# stepper_motor_driver_schem.net
KiCad netlist of a schematic drawn in EAGLE
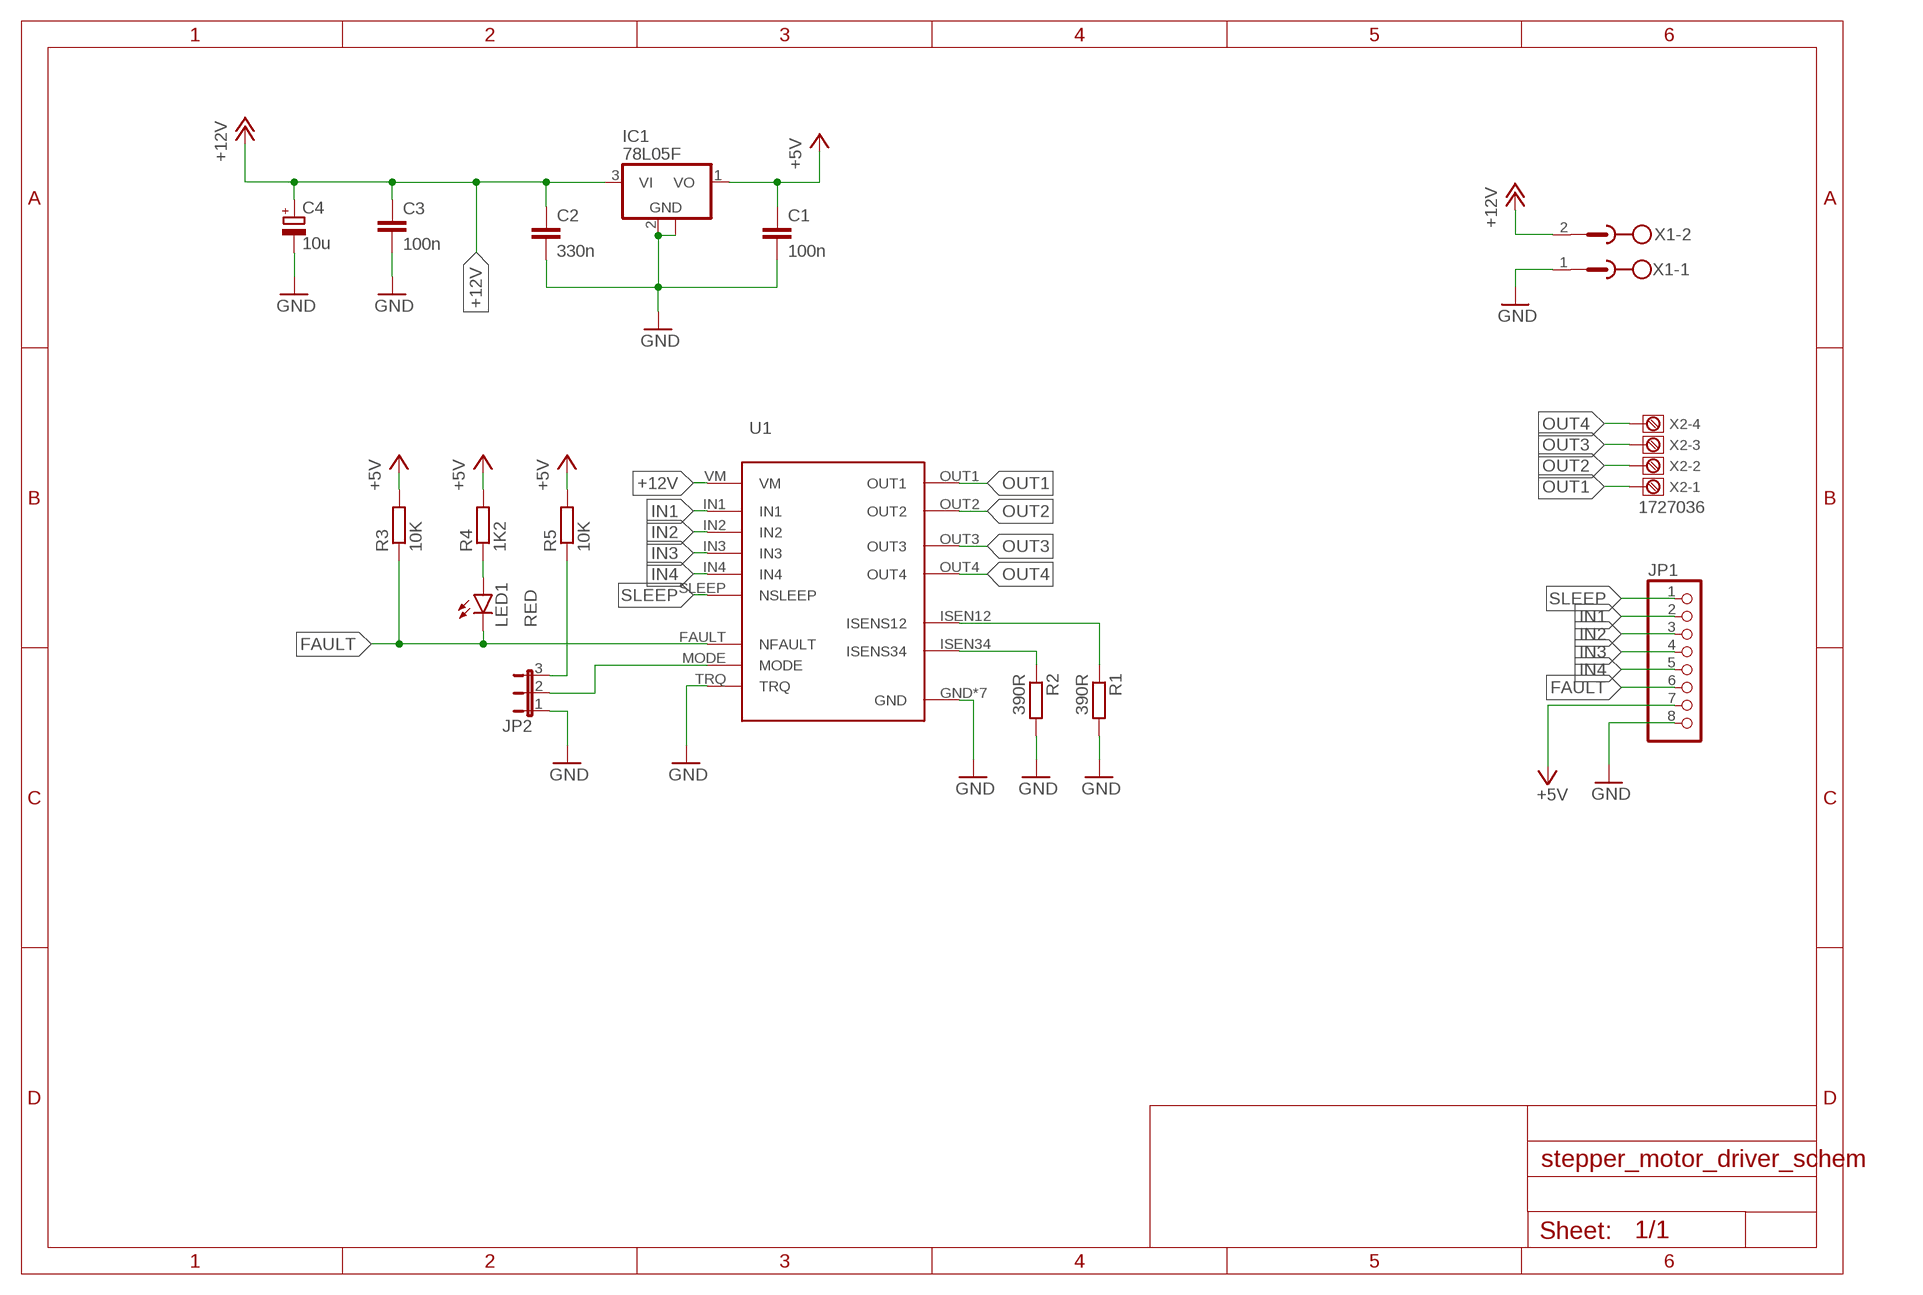
[diagram p0: schematic, sheet 1]

(export (version "E")
  (design (tool "Eeschema 10.0.6"))
  (components
    (comp (ref "C1")
      (value "100n")
      (footprint "eagle-import:C0402")
      (libsource (lib "eagle-import") (part "C-EUC0402"))
    )
    (comp (ref "C2")
      (value "330n")
      (footprint "eagle-import:C0402")
      (libsource (lib "eagle-import") (part "C-EUC0402"))
    )
    (comp (ref "C3")
      (value "100n")
      (footprint "eagle-import:C0402")
      (libsource (lib "eagle-import") (part "C-EUC0402"))
    )
    (comp (ref "C4")
      (value "10u")
      (footprint "eagle-import:E2-5")
      (libsource (lib "eagle-import") (part "CPOL-EUE2-5"))
    )
    (comp (ref "IC1")
      (value "78L05F")
      (footprint "eagle-import:SOT89")
      (libsource (lib "eagle-import") (part "78LF05"))
    )
    (comp (ref "JP1")
      (value "PINHD-1X8")
      (footprint "eagle-import:1X08")
      (libsource (lib "eagle-import") (part "PINHD-1X8"))
    )
    (comp (ref "JP2")
      (value "JP2E")
      (footprint "eagle-import:JP2")
      (libsource (lib "eagle-import") (part "JP2E"))
    )
    (comp (ref "LED1")
      (value "RED")
      (footprint "eagle-import:CHIP-LED0603")
      (libsource (lib "eagle-import") (part "LEDCHIP-LED0603"))
    )
    (comp (ref "R1")
      (value "390R")
      (footprint "eagle-import:R1206")
      (libsource (lib "eagle-import") (part "R-EU_R1206"))
    )
    (comp (ref "R2")
      (value "390R")
      (footprint "eagle-import:R1206")
      (libsource (lib "eagle-import") (part "R-EU_R1206"))
    )
    (comp (ref "R3")
      (value "10K")
      (footprint "eagle-import:R0603")
      (libsource (lib "eagle-import") (part "R-EU_R0603"))
    )
    (comp (ref "R4")
      (value "1K2")
      (footprint "eagle-import:R0603")
      (libsource (lib "eagle-import") (part "R-EU_R0603"))
    )
    (comp (ref "R5")
      (value "10K")
      (footprint "eagle-import:R0603")
      (libsource (lib "eagle-import") (part "R-EU_R0603"))
    )
    (comp (ref "U1")
      (value "DRV8847RTER")
      (footprint "eagle-import:DRV8847RTER")
      (libsource (lib "eagle-import") (part "DRV8847RTER"))
    )
    (comp (ref "X1")
      (value "MSTBV2")
      (footprint "eagle-import:MSTBV2")
      (libsource (lib "eagle-import") (part "MSTBV2"))
    )
    (comp (ref "X2")
      (value "1727036")
      (footprint "eagle-import:1727036")
      (fields (field (name "MF") "FARNELL"))
      (libsource (lib "eagle-import") (part "1727036"))
    )
  )
  (nets
    (net (code "1") (name "+5V") (class "Default")
      (node (ref "C1") (pin "1") (pinfunction "1_1") (pintype "passive"))
      (node (ref "IC1") (pin "1") (pinfunction "VO_1") (pintype "passive"))
      (node (ref "JP1") (pin "7") (pinfunction "7_7") (pintype "passive"))
      (node (ref "R3") (pin "2") (pinfunction "2_2") (pintype "passive"))
      (node (ref "R4") (pin "2") (pinfunction "2_2") (pintype "passive"))
      (node (ref "R5") (pin "2") (pinfunction "2_2") (pintype "passive"))
    )
    (net (code "2") (name "+12V") (class "Default")
      (node (ref "C2") (pin "1") (pinfunction "1_1") (pintype "passive"))
      (node (ref "C3") (pin "1") (pinfunction "1_1") (pintype "passive"))
      (node (ref "C4") (pin "+") (pinfunction "+_+") (pintype "passive"))
      (node (ref "IC1") (pin "3") (pinfunction "VI_3") (pintype "input"))
      (node (ref "U1") (pin "VM") (pinfunction "VM_VM") (pintype "bidirectional"))
      (node (ref "X1") (pin "2") (pinfunction "SK_2") (pintype "passive"))
    )
    (net (code "3") (name "FAULT") (class "Default")
      (node (ref "JP1") (pin "6") (pinfunction "6_6") (pintype "passive"))
      (node (ref "LED1") (pin "C") (pinfunction "C_C") (pintype "passive"))
      (node (ref "R3") (pin "1") (pinfunction "1_1") (pintype "passive"))
      (node (ref "U1") (pin "FAULT") (pinfunction "NFAULT_FAULT") (pintype "bidirectional"))
    )
    (net (code "4") (name "GND") (class "Default")
      (node (ref "C1") (pin "2") (pinfunction "2_2") (pintype "passive"))
      (node (ref "C2") (pin "2") (pinfunction "2_2") (pintype "passive"))
      (node (ref "C3") (pin "2") (pinfunction "2_2") (pintype "passive"))
      (node (ref "C4") (pin "-") (pinfunction "-_-") (pintype "passive"))
      (node (ref "IC1") (pin "2") (pinfunction "GND_2") (pintype "passive"))
      (node (ref "IC1") (pin "2@1") (pinfunction "GND_2@1") (pintype "passive"))
      (node (ref "JP1") (pin "8") (pinfunction "8_8") (pintype "passive"))
      (node (ref "JP2") (pin "1") (pinfunction "1_1") (pintype "passive"))
      (node (ref "R1") (pin "2") (pinfunction "2_2") (pintype "passive"))
      (node (ref "R2") (pin "2") (pinfunction "2_2") (pintype "passive"))
      (node (ref "U1") (pin "GND") (pinfunction "GND_GND") (pintype "bidirectional"))
      (node (ref "U1") (pin "T1") (pinfunction "GND_T1") (pintype "bidirectional"))
      (node (ref "U1") (pin "T2") (pinfunction "GND_T2") (pintype "bidirectional"))
      (node (ref "U1") (pin "T3") (pinfunction "GND_T3") (pintype "bidirectional"))
      (node (ref "U1") (pin "T4") (pinfunction "GND_T4") (pintype "bidirectional"))
      (node (ref "U1") (pin "T5") (pinfunction "GND_T5") (pintype "bidirectional"))
      (node (ref "U1") (pin "THERMAL_PAD") (pinfunction "GND_THERMAL_PAD") (pintype "bidirectional"))
      (node (ref "U1") (pin "TRQ") (pinfunction "TRQ_TRQ") (pintype "bidirectional"))
      (node (ref "X1") (pin "1") (pinfunction "SK_1") (pintype "passive"))
    )
    (net (code "5") (name "IN1") (class "Default")
      (node (ref "JP1") (pin "2") (pinfunction "2_2") (pintype "passive"))
      (node (ref "U1") (pin "IN1") (pinfunction "IN1_IN1") (pintype "bidirectional"))
    )
    (net (code "6") (name "IN2") (class "Default")
      (node (ref "JP1") (pin "3") (pinfunction "3_3") (pintype "passive"))
      (node (ref "U1") (pin "IN2") (pinfunction "IN2_IN2") (pintype "bidirectional"))
    )
    (net (code "7") (name "IN3") (class "Default")
      (node (ref "JP1") (pin "4") (pinfunction "4_4") (pintype "passive"))
      (node (ref "U1") (pin "IN3") (pinfunction "IN3_IN3") (pintype "bidirectional"))
    )
    (net (code "8") (name "IN4") (class "Default")
      (node (ref "JP1") (pin "5") (pinfunction "5_5") (pintype "passive"))
      (node (ref "U1") (pin "IN4") (pinfunction "IN4_IN4") (pintype "bidirectional"))
    )
    (net (code "9") (name "Net-(JP2-Pad2)") (class "Default")
      (node (ref "JP2") (pin "2") (pinfunction "2_2") (pintype "passive"))
      (node (ref "U1") (pin "MODE") (pinfunction "MODE_MODE") (pintype "bidirectional"))
    )
    (net (code "10") (name "Net-(JP2-Pad3)") (class "Default")
      (node (ref "JP2") (pin "3") (pinfunction "3_3") (pintype "passive"))
      (node (ref "R5") (pin "1") (pinfunction "1_1") (pintype "passive"))
    )
    (net (code "11") (name "Net-(LED1-PadA)") (class "Default")
      (node (ref "LED1") (pin "A") (pinfunction "A_A") (pintype "passive"))
      (node (ref "R4") (pin "1") (pinfunction "1_1") (pintype "passive"))
    )
    (net (code "12") (name "Net-(U1-ISENS12)") (class "Default")
      (node (ref "R1") (pin "1") (pinfunction "1_1") (pintype "passive"))
      (node (ref "U1") (pin "ISEN12") (pinfunction "ISENS12_ISEN12") (pintype "bidirectional"))
    )
    (net (code "13") (name "Net-(U1-ISENS34)") (class "Default")
      (node (ref "R2") (pin "1") (pinfunction "1_1") (pintype "passive"))
      (node (ref "U1") (pin "ISEN34") (pinfunction "ISENS34_ISEN34") (pintype "bidirectional"))
    )
    (net (code "14") (name "OUT1") (class "Default")
      (node (ref "U1") (pin "OUT1") (pinfunction "OUT1_OUT1") (pintype "bidirectional"))
      (node (ref "X2") (pin "1") (pinfunction "1_1") (pintype "passive"))
    )
    (net (code "15") (name "OUT2") (class "Default")
      (node (ref "U1") (pin "OUT2") (pinfunction "OUT2_OUT2") (pintype "bidirectional"))
      (node (ref "X2") (pin "2") (pinfunction "1_2") (pintype "passive"))
    )
    (net (code "16") (name "OUT3") (class "Default")
      (node (ref "U1") (pin "OUT3") (pinfunction "OUT3_OUT3") (pintype "bidirectional"))
      (node (ref "X2") (pin "3") (pinfunction "1_3") (pintype "passive"))
    )
    (net (code "17") (name "OUT4") (class "Default")
      (node (ref "U1") (pin "OUT4") (pinfunction "OUT4_OUT4") (pintype "bidirectional"))
      (node (ref "X2") (pin "4") (pinfunction "1_4") (pintype "passive"))
    )
    (net (code "18") (name "SLEEP") (class "Default")
      (node (ref "JP1") (pin "1") (pinfunction "1_1") (pintype "passive"))
      (node (ref "U1") (pin "SLEEP") (pinfunction "NSLEEP_SLEEP") (pintype "bidirectional"))
    )
  )
)
